# miniPCIe_EC200U.net
KiCad netlist of a schematic drawn in Altium Designer
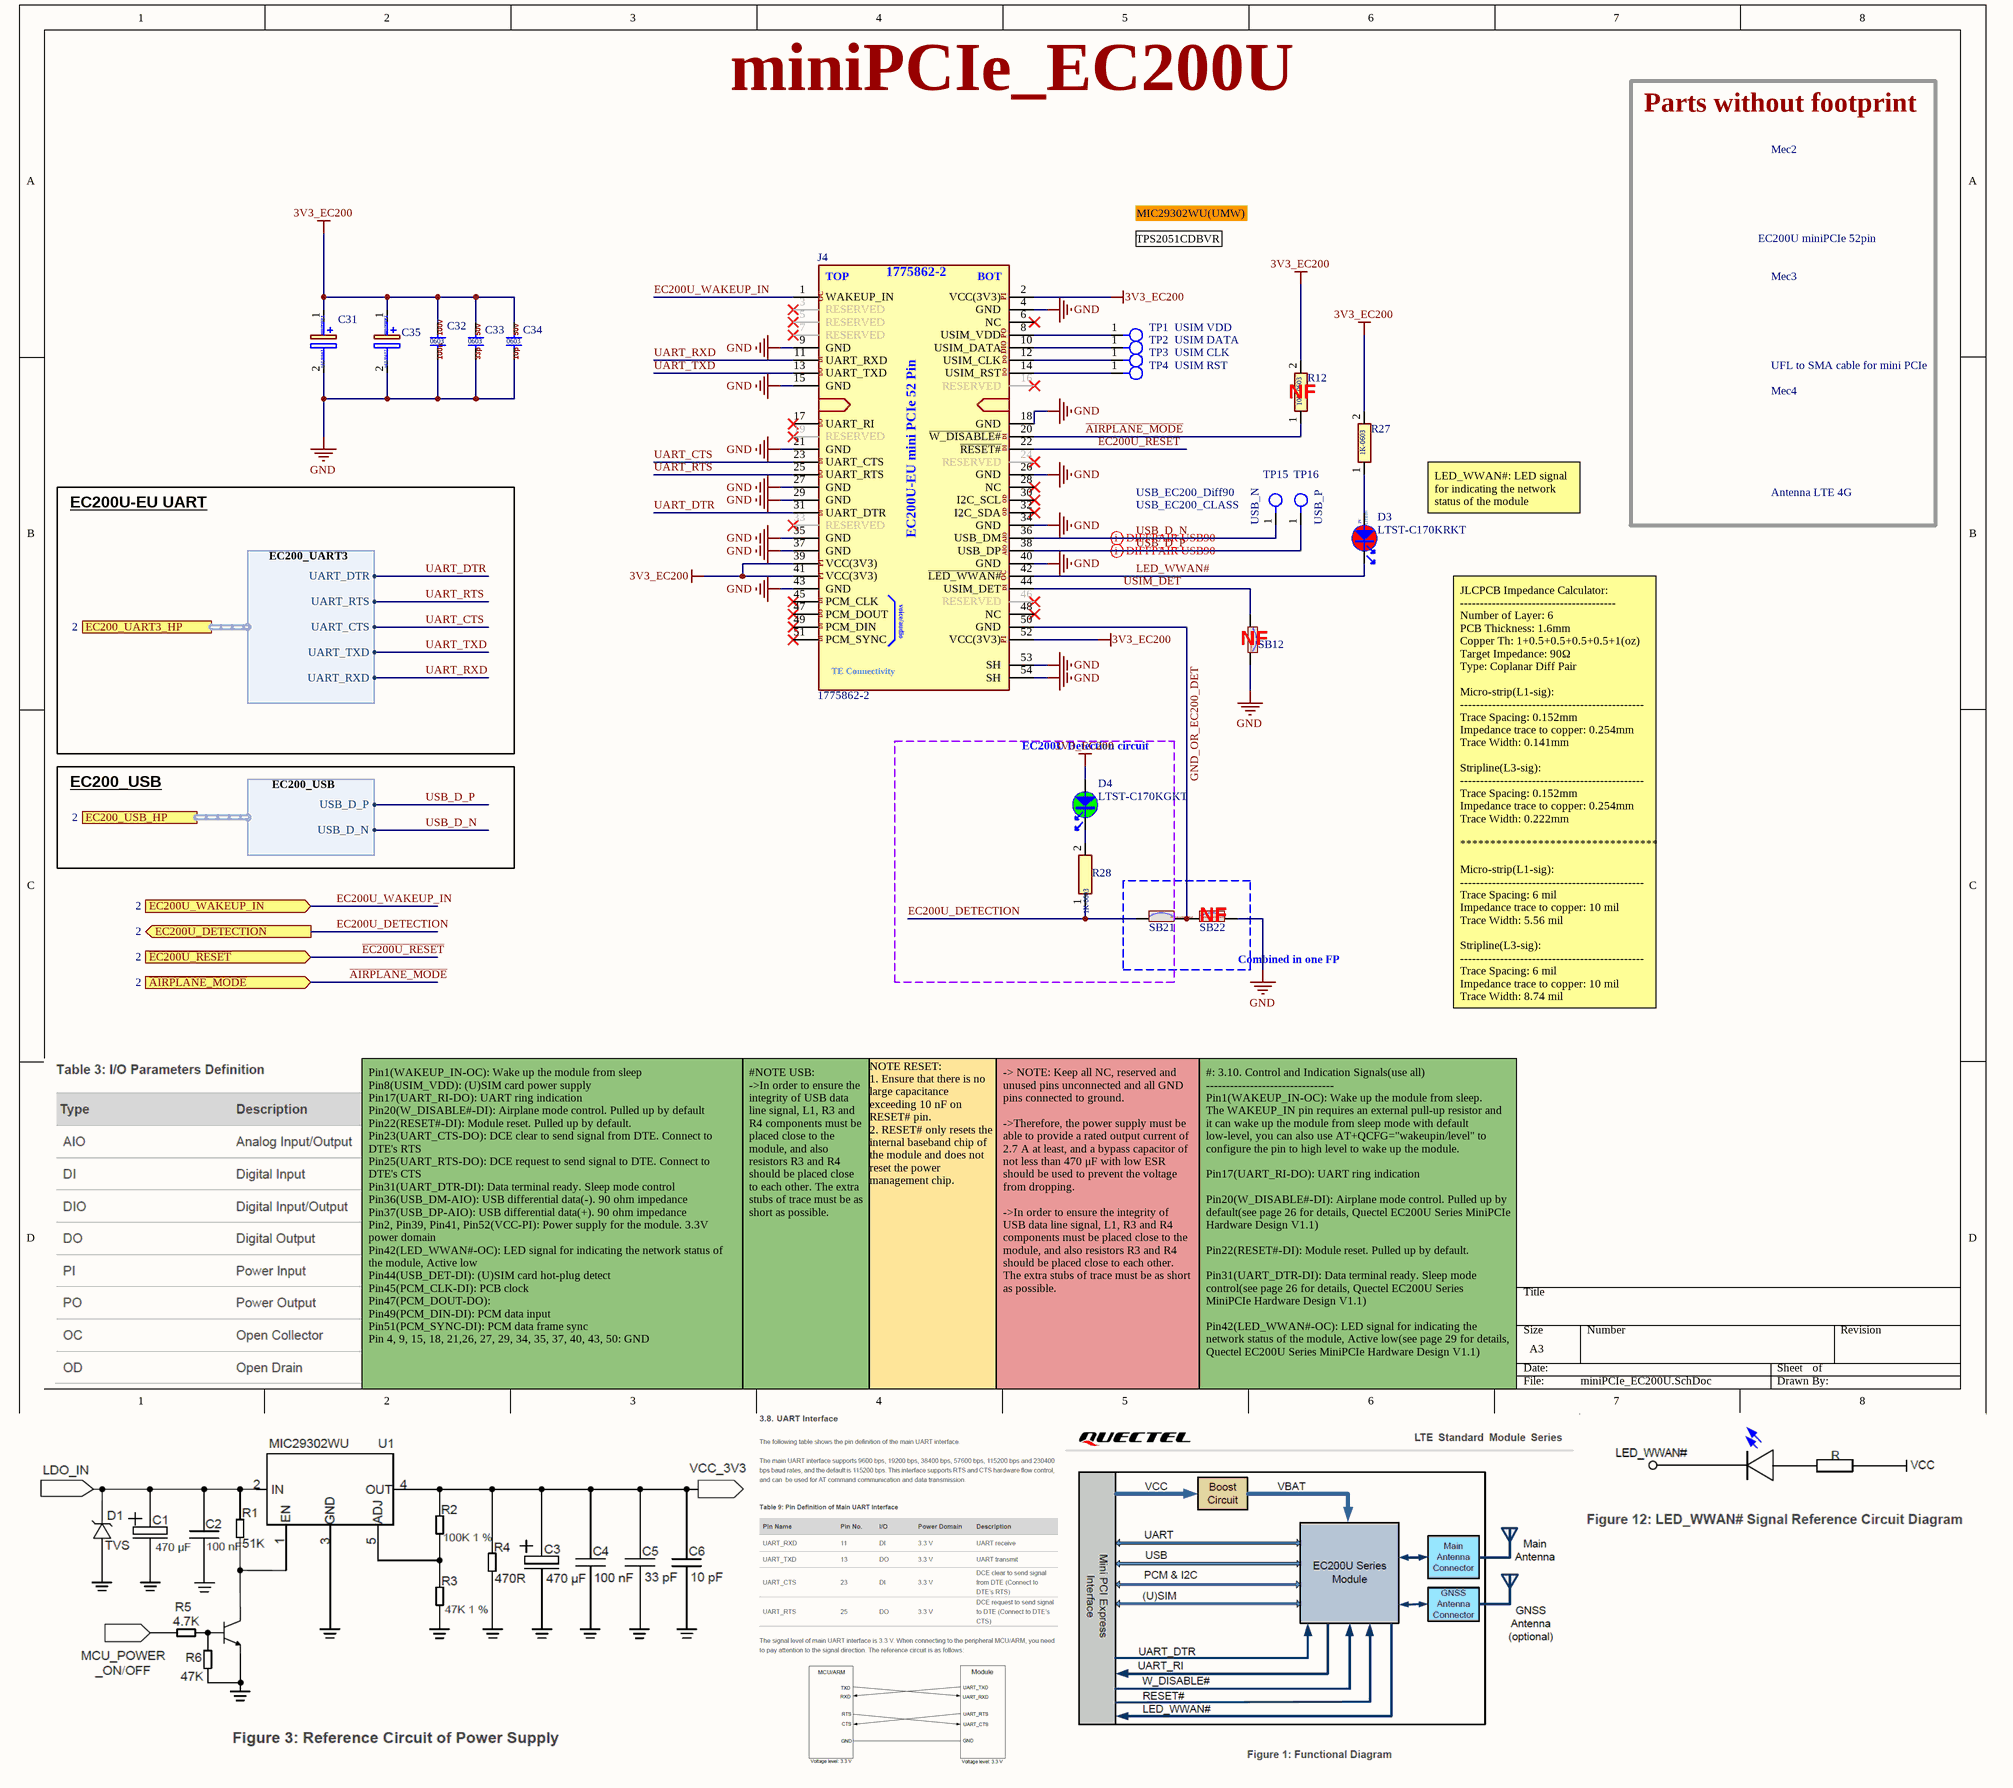
[diagram p0: miniPCIe_EC200U.SchDoc]

(export (version "E")
  (design (tool "Eeschema 10.0.6"))
  (components
    (comp (ref "C31")
      (value "TAJC107K010RNJ")
      (footprint "CASE-C-6032")
      (description "CAP: TANT 100uF ±10% 10V CASE-C-6032")
      (fields (field (name "LCSC PART #") "C8649"))
      (libsource (lib "Nadim Altium Lib-Univ") (part "TAJC107K010RNJ"))
    )
    (comp (ref "C32")
      (value "CL10B104KC8NNNC")
      (footprint "0603-CAP")
      (description "CAP: CER 100NF 100V X7R 0603")
      (fields (field (name "LCSC PART #") "C15725"))
      (libsource (lib "Nadim Altium Lib-Univ") (part "CL10B104KC8NNNC"))
    )
    (comp (ref "C33")
      (value "CL10C330JB8NNNC")
      (footprint "0603-CAP")
      (description "CAP: CER 33PF 50V C0G 0603")
      (fields (field (name "LCSC PART #") "C1663"))
      (libsource (lib "Nadim Altium Lib-Univ") (part "CL10C330JB8NNNC"))
    )
    (comp (ref "C34")
      (value "CL10C100JB8NNNC")
      (footprint "0603-CAP")
      (description "CAP: CER 10PF 50V C0G 0603")
      (fields (field (name "LCSC PART #") "C1634"))
      (libsource (lib "Nadim Altium Lib-Univ") (part "CL10C100JB8NNNC"))
    )
    (comp (ref "C35")
      (value "TAJD227K010RNJ")
      (footprint "Nadim Altium Lib-Univ:CASE-D-7343")
      (description "CAP: TANT 220uF ±10% 10V CASE-D-7343")
      (fields (field (name "LCSC PART #") "C8024"))
      (libsource (lib "Nadim Altium Lib-Univ") (part "TAJD227K010RNJ"))
    )
    (comp (ref "D3")
      (value "LTST-C170KRKT")
      (footprint "0805-LED-RED")
      (description "LED: RED 20mA 54mcd Colorless Transparent Lens -55℃~+85℃ 631nm Red 130° 75mW 2V 0805 LED")
      (fields (field (name "LCSC PART #") "C94868"))
      (libsource (lib "Nadim Altium Lib-Univ") (part "LTST-C170KRKT"))
    )
    (comp (ref "D4")
      (value "LTST-C170KGKT")
      (footprint "0805-LED-BLUE")
      (fields (field (name "LCSC PART #") "C98221"))
      (libsource (lib "Nadim Altium Lib-Univ") (part "LTST-C170KGKT"))
    )
    (comp (ref "J4")
      (value "1775862-2")
      (footprint "Nadim Altium Lib-Univ:mini PCIe 52p 67910-5700")
      (fields (field (name "LCSC PART #") "C428486"))
      (libsource (lib "Nadim Altium Lib-Univ") (part "1775862-2"))
    )
    (comp (ref "Mec2")
      (value "EC200U miniPCIe 52pin")
      (footprint "mini PCIe 52pin Module")
      (description "MODULE: Quectel EC200U miniPCIe 52pin 4G LTE GSM, PCIe,")
      (libsource (lib "Nadim Altium Lib-Univ") (part "EC200U miniPCIe 52pin"))
    )
    (comp (ref "Mec3")
      (value "UFL to SMA cable for mini PCIe")
      (description "Antenna: UFL to SMA cable for mini PCIe")
      (libsource (lib "Nadim Altium Lib-Univ") (part "UFL to SMA"))
    )
    (comp (ref "Mec4")
      (value "Antenna LTE 4G")
      (libsource (lib "Nadim Altium Lib-Univ") (part "Antenna LTE 4G"))
    )
    (comp (ref "R12")
      (value "0603WAF1002T5E")
      (footprint "0603-RES")
      (description "RES: 10K OHM 1% 100mW 0603 75V")
      (fields (field (name "LCSC PART #") "C25804"))
      (libsource (lib "Nadim Altium Lib-Univ") (part "0603WAF1002T5E"))
    )
    (comp (ref "R27")
      (value "0603WAF1001T5E")
      (footprint "0603-RES")
      (description "RES: 1K OHM 1% 100mW 0603 75V")
      (fields (field (name "LCSC PART #") "C21190"))
      (libsource (lib "Nadim Altium Lib-Univ") (part "0603WAF1001T5E"))
    )
    (comp (ref "R28")
      (value "0603WAF1001T5E")
      (footprint "0603-RES")
      (description "RES: 1K OHM 1% 100mW 0603 75V")
      (fields (field (name "LCSC PART #") "C21190"))
      (libsource (lib "") (part "0603WAF1001T5E_1"))
    )
    (comp (ref "SB12")
      (value "0603WAF0000T5E")
      (footprint "SOLDER-BRIDGE_R0603-0R")
      (description "Solder Bridge: ON SB 0603")
      (fields (field (name "LCSC PART #") "C21189"))
      (libsource (lib "") (part "0603WAF0000T5E_1"))
    )
    (comp (ref "SB21")
      (value "0603WAF0000T5E")
      (footprint "SOLDER-BRIDGE_R0603-0R")
      (description "Solder Bridge: ON SB 0603")
      (fields (field (name "LCSC PART #") "C21189"))
      (libsource (lib "") (part "0603WAF0000T5E_2"))
    )
    (comp (ref "SB22")
      (value "0603WAF0000T5E")
      (footprint "SOLDER-BRIDGE_R0603-0R")
      (description "Solder Bridge: ON SB 0603")
      (fields (field (name "LCSC PART #") "C21189"))
      (libsource (lib "Nadim Altium Lib-Univ") (part "0603WAF0000T5E"))
    )
    (comp (ref "TP1")
      (value "USIM VDD")
      (footprint "Test Pad FP")
      (description "TESTPAD: Test Pad")
      (libsource (lib "Nadim Altium Lib-Univ") (part "Test Pad"))
    )
    (comp (ref "TP2")
      (value "USIM DATA")
      (footprint "Test Pad FP")
      (description "TESTPAD: Test Pad")
      (libsource (lib "Nadim Altium Lib-Univ") (part "Test Pad"))
    )
    (comp (ref "TP3")
      (value "USIM CLK")
      (footprint "Test Pad FP")
      (description "TESTPAD: Test Pad")
      (libsource (lib "Nadim Altium Lib-Univ") (part "Test Pad"))
    )
    (comp (ref "TP4")
      (value "USIM RST")
      (footprint "Test Pad FP")
      (description "TESTPAD: Test Pad")
      (libsource (lib "Nadim Altium Lib-Univ") (part "Test Pad"))
    )
    (comp (ref "TP15")
      (value "USB_N")
      (footprint "Test Pad FP")
      (description "TESTPAD: Test Pad")
      (libsource (lib "Nadim Altium Lib-Univ") (part "Test Pad"))
    )
    (comp (ref "TP16")
      (value "USB_P")
      (footprint "Test Pad FP")
      (description "TESTPAD: Test Pad")
      (libsource (lib "Nadim Altium Lib-Univ") (part "Test Pad"))
    )
  )
  (nets
    (net (code "3") (name "/EC200U_DETECTION") (class "Default")
      (node (ref "R28") (pin "1") (pinfunction "1_1") (pintype "passive"))
      (node (ref "SB21") (pin "2") (pinfunction "2_2") (pintype "passive"))
    )
    (net (code "4") (name "/EC200U_WAKEUP_IN") (class "Default")
      (node (ref "J4") (pin "1") (pinfunction "WAKEUP_IN_1") (pintype "passive"))
    )
    (net (code "5") (name "/GND_OR_EC200_DET") (class "Default")
      (node (ref "J4") (pin "50") (pinfunction "GND_50") (pintype "passive"))
      (node (ref "SB21") (pin "1") (pinfunction "1_1") (pintype "passive"))
      (node (ref "SB22") (pin "1") (pinfunction "1_1") (pintype "passive"))
    )
    (net (code "6") (name "/LED_WWAN#") (class "Default")
      (node (ref "D3") (pin "2") (pintype "passive"))
      (node (ref "J4") (pin "42") (pinfunction "~{LED_WWAN#}_42") (pintype "passive"))
    )
    (net (code "7") (name "/UART_CTS") (class "Default")
      (node (ref "J4") (pin "23") (pinfunction "UART_CTS_23") (pintype "passive"))
    )
    (net (code "8") (name "/UART_DTR") (class "Default")
      (node (ref "J4") (pin "31") (pinfunction "UART_DTR_31") (pintype "passive"))
    )
    (net (code "9") (name "/UART_RTS") (class "Default")
      (node (ref "J4") (pin "25") (pinfunction "UART_RTS_25") (pintype "passive"))
    )
    (net (code "10") (name "/UART_RXD") (class "Default")
      (node (ref "J4") (pin "11") (pinfunction "UART_RXD_11") (pintype "passive"))
    )
    (net (code "11") (name "/UART_TXD") (class "Default")
      (node (ref "J4") (pin "13") (pinfunction "UART_TXD_13") (pintype "passive"))
    )
    (net (code "12") (name "/USB_D_N") (class "Default")
      (node (ref "J4") (pin "36") (pinfunction "USB_DM_36") (pintype "passive"))
      (node (ref "TP15") (pin "1") (pinfunction "1_1") (pintype "passive"))
    )
    (net (code "13") (name "/USB_D_P") (class "Default")
      (node (ref "J4") (pin "38") (pinfunction "USB_DP_38") (pintype "passive"))
      (node (ref "TP16") (pin "1") (pinfunction "1_1") (pintype "passive"))
    )
    (net (code "14") (name "/USIM_DET") (class "Default")
      (node (ref "J4") (pin "44") (pinfunction "USIM_DET_44") (pintype "passive"))
      (node (ref "SB12") (pin "1") (pinfunction "1_1") (pintype "passive"))
    )
    (net (code "17") (name "/~{AIRPLANE_MODE}") (class "Default")
      (node (ref "J4") (pin "20") (pinfunction "~{W_DISABLE#}_20") (pintype "passive"))
      (node (ref "R12") (pin "1") (pinfunction "1_1") (pintype "passive"))
    )
    (net (code "18") (name "/~{EC200U_RESET}") (class "Default")
      (node (ref "J4") (pin "22") (pinfunction "~{RESET#}_22") (pintype "passive"))
    )
    (net (code "19") (name "3V3_EC200") (class "Default")
      (node (ref "C31") (pin "1") (pinfunction "+_1") (pintype "passive"))
      (node (ref "C32") (pin "2") (pinfunction "2_2") (pintype "passive"))
      (node (ref "C33") (pin "2") (pinfunction "2_2") (pintype "passive"))
      (node (ref "C34") (pin "2") (pinfunction "2_2") (pintype "passive"))
      (node (ref "C35") (pin "1") (pinfunction "+_1") (pintype "passive"))
      (node (ref "D4") (pin "1") (pintype "passive"))
      (node (ref "J4") (pin "2") (pinfunction "VCC(3V3)_2") (pintype "passive"))
      (node (ref "J4") (pin "39") (pinfunction "VCC(3V3)_39") (pintype "passive"))
      (node (ref "J4") (pin "41") (pinfunction "VCC(3V3)_41") (pintype "passive"))
      (node (ref "J4") (pin "52") (pinfunction "VCC(3V3)_52") (pintype "passive"))
      (node (ref "R12") (pin "2") (pinfunction "2_2") (pintype "passive"))
      (node (ref "R27") (pin "2") (pinfunction "2_2") (pintype "passive"))
    )
    (net (code "20") (name "GND") (class "Default")
      (node (ref "C31") (pin "2") (pinfunction "-_2") (pintype "passive"))
      (node (ref "C32") (pin "1") (pinfunction "1_1") (pintype "passive"))
      (node (ref "C33") (pin "1") (pinfunction "1_1") (pintype "passive"))
      (node (ref "C34") (pin "1") (pinfunction "1_1") (pintype "passive"))
      (node (ref "C35") (pin "2") (pinfunction "-_2") (pintype "passive"))
      (node (ref "J4") (pin "15") (pinfunction "GND_15") (pintype "passive"))
      (node (ref "J4") (pin "18") (pinfunction "GND_18") (pintype "passive"))
      (node (ref "J4") (pin "21") (pinfunction "GND_21") (pintype "passive"))
      (node (ref "J4") (pin "26") (pinfunction "GND_26") (pintype "passive"))
      (node (ref "J4") (pin "27") (pinfunction "GND_27") (pintype "passive"))
      (node (ref "J4") (pin "29") (pinfunction "GND_29") (pintype "passive"))
      (node (ref "J4") (pin "34") (pinfunction "GND_34") (pintype "passive"))
      (node (ref "J4") (pin "35") (pinfunction "GND_35") (pintype "passive"))
      (node (ref "J4") (pin "37") (pinfunction "GND_37") (pintype "passive"))
      (node (ref "J4") (pin "4") (pinfunction "GND_4") (pintype "passive"))
      (node (ref "J4") (pin "40") (pinfunction "GND_40") (pintype "passive"))
      (node (ref "J4") (pin "43") (pinfunction "GND_43") (pintype "passive"))
      (node (ref "J4") (pin "53") (pinfunction "SH_53") (pintype "passive"))
      (node (ref "J4") (pin "54") (pinfunction "SH_54") (pintype "passive"))
      (node (ref "J4") (pin "9") (pinfunction "GND_9") (pintype "passive"))
      (node (ref "SB12") (pin "2") (pinfunction "2_2") (pintype "passive"))
      (node (ref "SB22") (pin "2") (pinfunction "2_2") (pintype "passive"))
    )
    (net (code "21") (name "Net-(D3-Pad1)") (class "Default")
      (node (ref "D3") (pin "1") (pintype "passive"))
      (node (ref "R27") (pin "1") (pinfunction "1_1") (pintype "passive"))
    )
    (net (code "22") (name "Net-(D4-Pad2)") (class "Default")
      (node (ref "D4") (pin "2") (pintype "passive"))
      (node (ref "R28") (pin "2") (pinfunction "2_2") (pintype "passive"))
    )
    (net (code "23") (name "Net-(J4-USIM_CLK)") (class "Default")
      (node (ref "J4") (pin "12") (pinfunction "USIM_CLK_12") (pintype "passive"))
      (node (ref "TP3") (pin "1") (pinfunction "1_1") (pintype "passive"))
    )
    (net (code "24") (name "Net-(J4-USIM_DATA)") (class "Default")
      (node (ref "J4") (pin "10") (pinfunction "USIM_DATA_10") (pintype "passive"))
      (node (ref "TP2") (pin "1") (pinfunction "1_1") (pintype "passive"))
    )
    (net (code "25") (name "Net-(J4-USIM_RST)") (class "Default")
      (node (ref "J4") (pin "14") (pinfunction "USIM_RST_14") (pintype "passive"))
      (node (ref "TP4") (pin "1") (pinfunction "1_1") (pintype "passive"))
    )
    (net (code "26") (name "Net-(J4-USIM_VDD)") (class "Default")
      (node (ref "J4") (pin "8") (pinfunction "USIM_VDD_8") (pintype "passive"))
      (node (ref "TP1") (pin "1") (pinfunction "1_1") (pintype "passive"))
    )
    (net (code "27") (name "unconnected-(J4-I2C_SCL-Pad30)") (class "Default")
      (node (ref "J4") (pin "30") (pinfunction "I2C_SCL_30") (pintype "passive+no_connect"))
    )
    (net (code "28") (name "unconnected-(J4-I2C_SDA-Pad32)") (class "Default")
      (node (ref "J4") (pin "32") (pinfunction "I2C_SDA_32") (pintype "passive+no_connect"))
    )
    (net (code "29") (name "unconnected-(J4-NC-Pad6)") (class "Default")
      (node (ref "J4") (pin "6") (pinfunction "NC_6") (pintype "passive+no_connect"))
    )
    (net (code "30") (name "unconnected-(J4-NC-Pad28)") (class "Default")
      (node (ref "J4") (pin "28") (pinfunction "NC_28") (pintype "passive+no_connect"))
    )
    (net (code "31") (name "unconnected-(J4-NC-Pad48)") (class "Default")
      (node (ref "J4") (pin "48") (pinfunction "NC_48") (pintype "passive+no_connect"))
    )
    (net (code "32") (name "unconnected-(J4-PCM_CLK-Pad45)") (class "Default")
      (node (ref "J4") (pin "45") (pinfunction "PCM_CLK_45") (pintype "passive+no_connect"))
    )
    (net (code "33") (name "unconnected-(J4-PCM_DIN-Pad49)") (class "Default")
      (node (ref "J4") (pin "49") (pinfunction "PCM_DIN_49") (pintype "passive+no_connect"))
    )
    (net (code "34") (name "unconnected-(J4-PCM_DOUT-Pad47)") (class "Default")
      (node (ref "J4") (pin "47") (pinfunction "PCM_DOUT_47") (pintype "passive+no_connect"))
    )
    (net (code "35") (name "unconnected-(J4-PCM_SYNC-Pad51)") (class "Default")
      (node (ref "J4") (pin "51") (pinfunction "PCM_SYNC_51") (pintype "passive+no_connect"))
    )
    (net (code "36") (name "unconnected-(J4-RESERVED-Pad3)") (class "Default")
      (node (ref "J4") (pin "3") (pinfunction "RESERVED_3") (pintype "passive+no_connect"))
    )
    (net (code "37") (name "unconnected-(J4-RESERVED-Pad5)") (class "Default")
      (node (ref "J4") (pin "5") (pinfunction "RESERVED_5") (pintype "passive+no_connect"))
    )
    (net (code "38") (name "unconnected-(J4-RESERVED-Pad7)") (class "Default")
      (node (ref "J4") (pin "7") (pinfunction "RESERVED_7") (pintype "passive+no_connect"))
    )
    (net (code "39") (name "unconnected-(J4-RESERVED-Pad16)") (class "Default")
      (node (ref "J4") (pin "16") (pinfunction "RESERVED_16") (pintype "passive+no_connect"))
    )
    (net (code "40") (name "unconnected-(J4-RESERVED-Pad19)") (class "Default")
      (node (ref "J4") (pin "19") (pinfunction "RESERVED_19") (pintype "passive+no_connect"))
    )
    (net (code "41") (name "unconnected-(J4-RESERVED-Pad24)") (class "Default")
      (node (ref "J4") (pin "24") (pinfunction "RESERVED_24") (pintype "passive+no_connect"))
    )
    (net (code "42") (name "unconnected-(J4-RESERVED-Pad33)") (class "Default")
      (node (ref "J4") (pin "33") (pinfunction "RESERVED_33") (pintype "passive+no_connect"))
    )
    (net (code "43") (name "unconnected-(J4-RESERVED-Pad46)") (class "Default")
      (node (ref "J4") (pin "46") (pinfunction "RESERVED_46") (pintype "passive+no_connect"))
    )
    (net (code "44") (name "unconnected-(J4-UART_RI-Pad17)") (class "Default")
      (node (ref "J4") (pin "17") (pinfunction "UART_RI_17") (pintype "passive+no_connect"))
    )
  )
)
